# ospi144.net
KiCad netlist of a schematic drawn in EAGLE
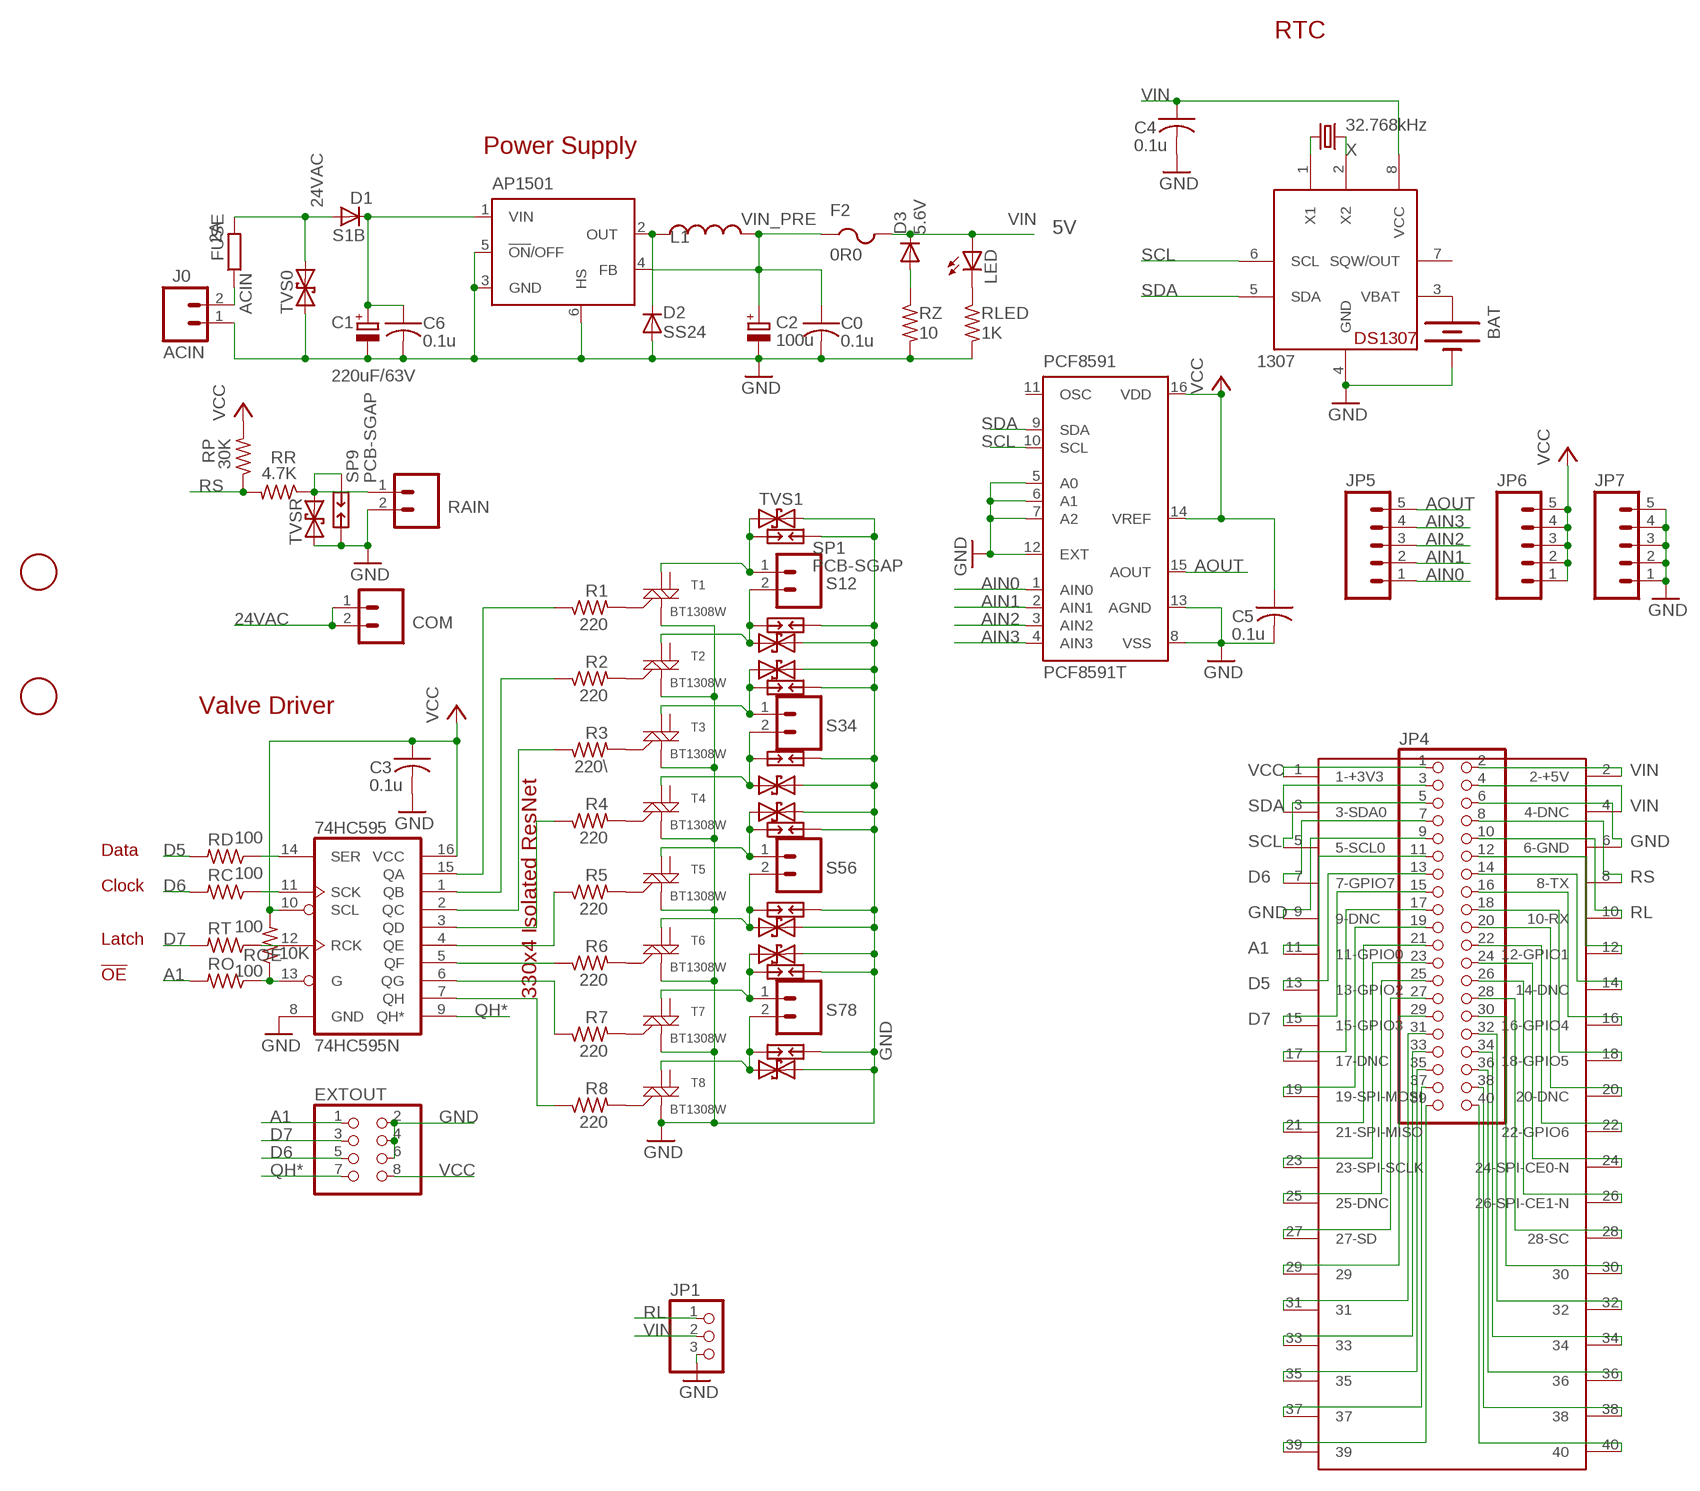
[diagram p0: schematic, sheet 1]

(export (version "E")
  (design (tool "Eeschema 10.0.6"))
  (components
    (comp (ref "74HC595")
      (value "74HC595N")
      (footprint "eagle-import:SO16")
      (libsource (lib "eagle-import") (part "74595DLS"))
    )
    (comp (ref "1307")
      (value "DS1307")
      (footprint "eagle-import:SO08")
      (libsource (lib "eagle-import") (part "DS1307SOIC"))
    )
    (comp (ref "AP1501")
      (value "LM2596S")
      (footprint "eagle-import:TO263-5")
      (fields (field (name "MF") "NATIONAL SEMICONDUCTOR") (field (name "MPN") "LM2596S-ADJ/NOPB"))
      (libsource (lib "eagle-import") (part "LM2596S"))
    )
    (comp (ref "BAT")
      (value "BATTERYBATTERY_12MM_SMT")
      (footprint "eagle-import:BATTCON_12MM_SMT")
      (libsource (lib "eagle-import") (part "BATTERYBATTERY_12MM_SMT"))
    )
    (comp (ref "C0")
      (value "0.1u")
      (footprint "eagle-import:C0603K")
      (libsource (lib "eagle-import") (part "C-USC0603K"))
    )
    (comp (ref "C1")
      (value "220uF/63V")
      (footprint "eagle-import:PANASONIC_E")
      (libsource (lib "eagle-import") (part "CPOL-EUE"))
    )
    (comp (ref "C2")
      (value "100u")
      (footprint "eagle-import:PANASONIC_E")
      (libsource (lib "eagle-import") (part "CPOL-EUE"))
    )
    (comp (ref "C3")
      (value "0.1u")
      (footprint "eagle-import:C0603K")
      (libsource (lib "eagle-import") (part "C-USC0603K"))
    )
    (comp (ref "C4")
      (value "0.1u")
      (footprint "eagle-import:C0603K")
      (libsource (lib "eagle-import") (part "C-USC0603K"))
    )
    (comp (ref "C5")
      (value "0.1u")
      (footprint "eagle-import:C0603K")
      (libsource (lib "eagle-import") (part "C-USC0603K"))
    )
    (comp (ref "C6")
      (value "0.1u")
      (footprint "eagle-import:C0603K")
      (libsource (lib "eagle-import") (part "C-USC0603K"))
    )
    (comp (ref "COM")
      (value "M025MM-X")
      (footprint "eagle-import:SCREWTERMINAL-5MM-2-X")
      (libsource (lib "eagle-import") (part "M025MM-X"))
    )
    (comp (ref "D1")
      (value "S1B")
      (footprint "eagle-import:DO-214AC")
      (libsource (lib "eagle-import") (part "DIODE-DO-214AC"))
    )
    (comp (ref "D2")
      (value "SS24")
      (footprint "eagle-import:SMB")
      (libsource (lib "eagle-import") (part "DIODE-SMB"))
    )
    (comp (ref "D3")
      (value "5.6V")
      (footprint "eagle-import:MINIMELF")
      (libsource (lib "eagle-import") (part "DIODE-MINIMELF"))
    )
    (comp (ref "EXTOUT")
      (value "PINHD-2X4/90")
      (footprint "eagle-import:2X04_90")
      (libsource (lib "eagle-import") (part "PINHD-2X4/90"))
    )
    (comp (ref "F2")
      (value "0R0")
      (footprint "eagle-import:1812")
      (libsource (lib "eagle-import") (part "PTCFUSE-1812"))
    )
    (comp (ref "FUSE")
      (value "2A")
      (footprint "eagle-import:0207_12")
      (libsource (lib "eagle-import") (part "R-EU_0207/12"))
    )
    (comp (ref "J0")
      (value "ACIN")
      (footprint "eagle-import:SCREWTERMINAL-4MM-2-X")
      (libsource (lib "eagle-import") (part "M024MM-X"))
    )
    (comp (ref "JP1")
      (value "PINHD-1X3")
      (footprint "eagle-import:1X03")
      (libsource (lib "eagle-import") (part "PINHD-1X3"))
    )
    (comp (ref "JP4")
      (value "PINHD-2X20")
      (footprint "eagle-import:2X20")
      (libsource (lib "eagle-import") (part "PINHD-2X20"))
    )
    (comp (ref "JP5")
      (value "M05PTH")
      (footprint "eagle-import:1X05")
      (libsource (lib "eagle-import") (part "M05PTH"))
    )
    (comp (ref "JP6")
      (value "M05PTH")
      (footprint "eagle-import:1X05")
      (libsource (lib "eagle-import") (part "M05PTH"))
    )
    (comp (ref "JP7")
      (value "M05PTH")
      (footprint "eagle-import:1X05")
      (libsource (lib "eagle-import") (part "M05PTH"))
    )
    (comp (ref "L1")
      (value "150uH")
      (footprint "eagle-import:CDRH125")
      (libsource (lib "eagle-import") (part "INDUCTORPWR"))
    )
    (comp (ref "LED")
      (value "LEDCHIPLED_0805")
      (footprint "eagle-import:CHIPLED_0805")
      (libsource (lib "eagle-import") (part "LEDCHIPLED_0805"))
    )
    (comp (ref "PCF8591")
      (value "PCF8591T")
      (footprint "eagle-import:SO16W")
      (fields (field (name "MPN") "PCF8591T/2,512"))
      (libsource (lib "eagle-import") (part "PCF8591T"))
    )
    (comp (ref "R1")
      (value "220")
      (footprint "eagle-import:R0603")
      (libsource (lib "eagle-import") (part "R-US_R0603"))
    )
    (comp (ref "R2")
      (value "220")
      (footprint "eagle-import:R0603")
      (libsource (lib "eagle-import") (part "R-US_R0603"))
    )
    (comp (ref "R3")
      (value "220\\")
      (footprint "eagle-import:R0603")
      (libsource (lib "eagle-import") (part "R-US_R0603"))
    )
    (comp (ref "R4")
      (value "220")
      (footprint "eagle-import:R0603")
      (libsource (lib "eagle-import") (part "R-US_R0603"))
    )
    (comp (ref "R5")
      (value "220")
      (footprint "eagle-import:R0603")
      (libsource (lib "eagle-import") (part "R-US_R0603"))
    )
    (comp (ref "R6")
      (value "220")
      (footprint "eagle-import:R0603")
      (libsource (lib "eagle-import") (part "R-US_R0603"))
    )
    (comp (ref "R7")
      (value "220")
      (footprint "eagle-import:R0603")
      (libsource (lib "eagle-import") (part "R-US_R0603"))
    )
    (comp (ref "R8")
      (value "220")
      (footprint "eagle-import:R0603")
      (libsource (lib "eagle-import") (part "R-US_R0603"))
    )
    (comp (ref "RAIN")
      (value "M025MM-X")
      (footprint "eagle-import:SCREWTERMINAL-5MM-2-X")
      (libsource (lib "eagle-import") (part "M025MM-X"))
    )
    (comp (ref "RC")
      (value "100")
      (footprint "eagle-import:R0603")
      (libsource (lib "eagle-import") (part "R-US_R0603"))
    )
    (comp (ref "RD")
      (value "100")
      (footprint "eagle-import:R0603")
      (libsource (lib "eagle-import") (part "R-US_R0603"))
    )
    (comp (ref "RLED")
      (value "1K")
      (footprint "eagle-import:R0805")
      (libsource (lib "eagle-import") (part "R-US_R0805"))
    )
    (comp (ref "RO")
      (value "100")
      (footprint "eagle-import:R0603")
      (libsource (lib "eagle-import") (part "R-US_R0603"))
    )
    (comp (ref "ROE")
      (value "10K")
      (footprint "eagle-import:R0603")
      (libsource (lib "eagle-import") (part "R-US_R0603"))
    )
    (comp (ref "RP")
      (value "30K")
      (footprint "eagle-import:R0805")
      (libsource (lib "eagle-import") (part "R-US_R0805"))
    )
    (comp (ref "RR")
      (value "4.7K")
      (footprint "eagle-import:R0805")
      (libsource (lib "eagle-import") (part "R-US_R0805"))
    )
    (comp (ref "RT")
      (value "100")
      (footprint "eagle-import:R0603")
      (libsource (lib "eagle-import") (part "R-US_R0603"))
    )
    (comp (ref "RZ")
      (value "10")
      (footprint "eagle-import:R2010")
      (libsource (lib "eagle-import") (part "R-US_R2010"))
    )
    (comp (ref "S12")
      (value "M025MM-X")
      (footprint "eagle-import:SCREWTERMINAL-5MM-2-X")
      (libsource (lib "eagle-import") (part "M025MM-X"))
    )
    (comp (ref "S34")
      (value "M025MM-X")
      (footprint "eagle-import:SCREWTERMINAL-5MM-2-X")
      (libsource (lib "eagle-import") (part "M025MM-X"))
    )
    (comp (ref "S56")
      (value "M025MM-X")
      (footprint "eagle-import:SCREWTERMINAL-5MM-2-X")
      (libsource (lib "eagle-import") (part "M025MM-X"))
    )
    (comp (ref "S78")
      (value "M025MM-X")
      (footprint "eagle-import:SCREWTERMINAL-5MM-2-X")
      (libsource (lib "eagle-import") (part "M025MM-X"))
    )
    (comp (ref "SP1")
      (value "PCB-SGAP")
      (footprint "eagle-import:PCB-SGAP")
      (libsource (lib "eagle-import") (part "PCB-SGAP"))
    )
    (comp (ref "SP2")
      (value "PCB-SGAP")
      (footprint "eagle-import:PCB-SGAP")
      (libsource (lib "eagle-import") (part "PCB-SGAP"))
    )
    (comp (ref "SP3")
      (value "PCB-SGAP")
      (footprint "eagle-import:PCB-SGAP")
      (libsource (lib "eagle-import") (part "PCB-SGAP"))
    )
    (comp (ref "SP4")
      (value "PCB-SGAP")
      (footprint "eagle-import:PCB-SGAP")
      (libsource (lib "eagle-import") (part "PCB-SGAP"))
    )
    (comp (ref "SP5")
      (value "PCB-SGAP")
      (footprint "eagle-import:PCB-SGAP")
      (libsource (lib "eagle-import") (part "PCB-SGAP"))
    )
    (comp (ref "SP6")
      (value "PCB-SGAP")
      (footprint "eagle-import:PCB-SGAP")
      (libsource (lib "eagle-import") (part "PCB-SGAP"))
    )
    (comp (ref "SP7")
      (value "PCB-SGAP")
      (footprint "eagle-import:PCB-SGAP")
      (libsource (lib "eagle-import") (part "PCB-SGAP"))
    )
    (comp (ref "SP8")
      (value "PCB-SGAP")
      (footprint "eagle-import:PCB-SGAP")
      (libsource (lib "eagle-import") (part "PCB-SGAP"))
    )
    (comp (ref "SP9")
      (value "PCB-SGAP")
      (footprint "eagle-import:PCB-SGAP")
      (libsource (lib "eagle-import") (part "PCB-SGAP"))
    )
    (comp (ref "T1")
      (value "BT1308W")
      (footprint "eagle-import:SOT223")
      (libsource (lib "eagle-import") (part "MAC97SOT223"))
    )
    (comp (ref "T2")
      (value "BT1308W")
      (footprint "eagle-import:SOT223")
      (libsource (lib "eagle-import") (part "MAC97SOT223"))
    )
    (comp (ref "T3")
      (value "BT1308W")
      (footprint "eagle-import:SOT223")
      (libsource (lib "eagle-import") (part "MAC97SOT223"))
    )
    (comp (ref "T4")
      (value "BT1308W")
      (footprint "eagle-import:SOT223")
      (libsource (lib "eagle-import") (part "MAC97SOT223"))
    )
    (comp (ref "T5")
      (value "BT1308W")
      (footprint "eagle-import:SOT223")
      (libsource (lib "eagle-import") (part "MAC97SOT223"))
    )
    (comp (ref "T6")
      (value "BT1308W")
      (footprint "eagle-import:SOT223")
      (libsource (lib "eagle-import") (part "MAC97SOT223"))
    )
    (comp (ref "T7")
      (value "BT1308W")
      (footprint "eagle-import:SOT223")
      (libsource (lib "eagle-import") (part "MAC97SOT223"))
    )
    (comp (ref "T8")
      (value "BT1308W")
      (footprint "eagle-import:SOT223")
      (libsource (lib "eagle-import") (part "MAC97SOT223"))
    )
    (comp (ref "TVS0")
      (value "TVSSMB")
      (footprint "eagle-import:SMB")
      (libsource (lib "eagle-import") (part "TVSSMB"))
    )
    (comp (ref "TVS1")
      (value "TVSSMB")
      (footprint "eagle-import:SMB")
      (libsource (lib "eagle-import") (part "TVSSMB"))
    )
    (comp (ref "TVS2")
      (value "TVSSMB")
      (footprint "eagle-import:SMB")
      (libsource (lib "eagle-import") (part "TVSSMB"))
    )
    (comp (ref "TVS3")
      (value "TVSSMB")
      (footprint "eagle-import:SMB")
      (libsource (lib "eagle-import") (part "TVSSMB"))
    )
    (comp (ref "TVS4")
      (value "TVSSMB")
      (footprint "eagle-import:SMB")
      (libsource (lib "eagle-import") (part "TVSSMB"))
    )
    (comp (ref "TVS5")
      (value "TVSSMB")
      (footprint "eagle-import:SMB")
      (libsource (lib "eagle-import") (part "TVSSMB"))
    )
    (comp (ref "TVS6")
      (value "TVSSMB")
      (footprint "eagle-import:SMB")
      (libsource (lib "eagle-import") (part "TVSSMB"))
    )
    (comp (ref "TVS7")
      (value "TVSSMB")
      (footprint "eagle-import:SMB")
      (libsource (lib "eagle-import") (part "TVSSMB"))
    )
    (comp (ref "TVS8")
      (value "TVSSMB")
      (footprint "eagle-import:SMB")
      (libsource (lib "eagle-import") (part "TVSSMB"))
    )
    (comp (ref "TVSR")
      (value "TVSSMB")
      (footprint "eagle-import:SMB")
      (libsource (lib "eagle-import") (part "TVSSMB"))
    )
    (comp (ref "U$1")
      (value "FIDUCIAL")
      (footprint "eagle-import:FIDUCIAL_1MM")
      (libsource (lib "eagle-import") (part "FIDUCIAL"))
    )
    (comp (ref "U$2")
      (value "RPIB+")
      (footprint "eagle-import:RPIB+")
      (libsource (lib "eagle-import") (part "RPIB+"))
    )
    (comp (ref "U$3")
      (value "FIDUCIAL")
      (footprint "eagle-import:FIDUCIAL_1MM")
      (libsource (lib "eagle-import") (part "FIDUCIAL"))
    )
    (comp (ref "X")
      (value "32.768kHz")
      (footprint "eagle-import:MM20SS")
      (libsource (lib "eagle-import") (part "CRYSTALMM20SS"))
    )
  )
  (nets
    (net (code "1") (name "/24VAC") (class "Default")
      (node (ref "COM") (pin "1") (pinfunction "1_1") (pintype "passive"))
      (node (ref "COM") (pin "2") (pinfunction "2_2") (pintype "passive"))
      (node (ref "D1") (pin "A") (pinfunction "A_A") (pintype "passive"))
      (node (ref "FUSE") (pin "2") (pinfunction "2_2") (pintype "passive"))
      (node (ref "TVS0") (pin "C") (pinfunction "C_C") (pintype "passive"))
    )
    (net (code "2") (name "/A1") (class "Default")
      (node (ref "EXTOUT") (pin "1") (pinfunction "1_1") (pintype "passive"))
      (node (ref "JP4") (pin "11") (pinfunction "11_11") (pintype "passive"))
      (node (ref "RO") (pin "2") (pinfunction "2_2") (pintype "passive"))
      (node (ref "U$2") (pin "11") (pinfunction "11-GPIO0_11") (pintype "bidirectional"))
    )
    (net (code "3") (name "/ACIN") (class "Default")
      (node (ref "FUSE") (pin "1") (pinfunction "1_1") (pintype "passive"))
      (node (ref "J0") (pin "2") (pinfunction "2_2") (pintype "passive"))
    )
    (net (code "4") (name "/AIN0") (class "Default")
      (node (ref "JP5") (pin "1") (pinfunction "1_1") (pintype "passive"))
      (node (ref "PCF8591") (pin "1") (pinfunction "AIN0_1") (pintype "input"))
    )
    (net (code "5") (name "/AIN1") (class "Default")
      (node (ref "JP5") (pin "2") (pinfunction "2_2") (pintype "passive"))
      (node (ref "PCF8591") (pin "2") (pinfunction "AIN1_2") (pintype "input"))
    )
    (net (code "6") (name "/AIN2") (class "Default")
      (node (ref "JP5") (pin "3") (pinfunction "3_3") (pintype "passive"))
      (node (ref "PCF8591") (pin "3") (pinfunction "AIN2_3") (pintype "input"))
    )
    (net (code "7") (name "/AIN3") (class "Default")
      (node (ref "JP5") (pin "4") (pinfunction "4_4") (pintype "passive"))
      (node (ref "PCF8591") (pin "4") (pinfunction "AIN3_4") (pintype "input"))
    )
    (net (code "8") (name "/AOUT") (class "Default")
      (node (ref "JP5") (pin "5") (pinfunction "5_5") (pintype "passive"))
      (node (ref "PCF8591") (pin "15") (pinfunction "AOUT_15") (pintype "output"))
    )
    (net (code "9") (name "/D5") (class "Default")
      (node (ref "JP4") (pin "13") (pinfunction "13_13") (pintype "passive"))
      (node (ref "RD") (pin "2") (pinfunction "2_2") (pintype "passive"))
      (node (ref "U$2") (pin "13") (pinfunction "13-GPIO2_13") (pintype "bidirectional"))
    )
    (net (code "10") (name "/D6") (class "Default")
      (node (ref "EXTOUT") (pin "5") (pinfunction "5_5") (pintype "passive"))
      (node (ref "JP4") (pin "7") (pinfunction "7_7") (pintype "passive"))
      (node (ref "RC") (pin "2") (pinfunction "2_2") (pintype "passive"))
      (node (ref "U$2") (pin "7") (pinfunction "7-GPIO7_7") (pintype "bidirectional"))
    )
    (net (code "11") (name "/D7") (class "Default")
      (node (ref "EXTOUT") (pin "3") (pinfunction "3_3") (pintype "passive"))
      (node (ref "JP4") (pin "15") (pinfunction "15_15") (pintype "passive"))
      (node (ref "RT") (pin "2") (pinfunction "2_2") (pintype "passive"))
      (node (ref "U$2") (pin "15") (pinfunction "15-GPIO3_15") (pintype "bidirectional"))
    )
    (net (code "12") (name "/QH*") (class "Default")
      (node (ref "74HC595") (pin "9") (pinfunction "QH*_9") (pintype "tri_state"))
      (node (ref "EXTOUT") (pin "7") (pinfunction "7_7") (pintype "passive"))
    )
    (net (code "13") (name "/RL") (class "Default")
      (node (ref "JP1") (pin "1") (pinfunction "1_1") (pintype "passive"))
      (node (ref "JP4") (pin "10") (pinfunction "10_10") (pintype "passive"))
      (node (ref "U$2") (pin "10") (pinfunction "10-RX_10") (pintype "bidirectional"))
    )
    (net (code "14") (name "/RS") (class "Default")
      (node (ref "JP4") (pin "8") (pinfunction "8_8") (pintype "passive"))
      (node (ref "RP") (pin "1") (pinfunction "1_1") (pintype "passive"))
      (node (ref "RR") (pin "2") (pinfunction "2_2") (pintype "passive"))
      (node (ref "U$2") (pin "8") (pinfunction "8-TX_8") (pintype "bidirectional"))
    )
    (net (code "15") (name "/SCL") (class "Default")
      (node (ref "1307") (pin "6") (pinfunction "SCL_6") (pintype "bidirectional"))
      (node (ref "JP4") (pin "5") (pinfunction "5_5") (pintype "passive"))
      (node (ref "PCF8591") (pin "10") (pinfunction "SCL_10") (pintype "input"))
      (node (ref "U$2") (pin "5") (pinfunction "5-SCL0_5") (pintype "bidirectional"))
    )
    (net (code "16") (name "/SDA") (class "Default")
      (node (ref "1307") (pin "5") (pinfunction "SDA_5") (pintype "bidirectional"))
      (node (ref "JP4") (pin "3") (pinfunction "3_3") (pintype "passive"))
      (node (ref "PCF8591") (pin "9") (pinfunction "SDA_9") (pintype "bidirectional"))
      (node (ref "U$2") (pin "3") (pinfunction "3-SDA0_3") (pintype "bidirectional"))
    )
    (net (code "17") (name "/VIN") (class "Default")
      (node (ref "1307") (pin "8") (pinfunction "VCC_8") (pintype "power_in"))
      (node (ref "C4") (pin "1") (pinfunction "1_1") (pintype "passive"))
      (node (ref "D3") (pin "C") (pinfunction "C_C") (pintype "passive"))
      (node (ref "F2") (pin "2") (pinfunction "2_2") (pintype "passive"))
      (node (ref "JP1") (pin "2") (pinfunction "2_2") (pintype "passive"))
      (node (ref "JP4") (pin "2") (pinfunction "2_2") (pintype "passive"))
      (node (ref "JP4") (pin "4") (pinfunction "4_4") (pintype "passive"))
      (node (ref "LED") (pin "A") (pinfunction "A_A") (pintype "passive"))
      (node (ref "U$2") (pin "2") (pinfunction "2-+5V_2") (pintype "bidirectional"))
      (node (ref "U$2") (pin "4") (pinfunction "4-DNC_4") (pintype "bidirectional"))
    )
    (net (code "18") (name "/VIN_PRE") (class "Default")
      (node (ref "AP1501") (pin "4") (pinfunction "FB_4") (pintype "input"))
      (node (ref "C0") (pin "1") (pinfunction "1_1") (pintype "passive"))
      (node (ref "C2") (pin "+") (pinfunction "+_+") (pintype "passive"))
      (node (ref "F2") (pin "1") (pinfunction "1_1") (pintype "passive"))
      (node (ref "L1") (pin "2") (pinfunction "2_2") (pintype "passive"))
    )
    (net (code "19") (name "GND") (class "Default")
      (node (ref "1307") (pin "4") (pinfunction "GND_4") (pintype "power_in"))
      (node (ref "74HC595") (pin "8") (pinfunction "GND_8") (pintype "power_in"))
      (node (ref "AP1501") (pin "3") (pinfunction "GND_3") (pintype "power_in"))
      (node (ref "AP1501") (pin "5") (pinfunction "~{ON}/OFF_5") (pintype "input"))
      (node (ref "AP1501") (pin "6") (pinfunction "HS_6") (pintype "power_in"))
      (node (ref "BAT") (pin "P$1") (pinfunction "-_P$1") (pintype "power_in"))
      (node (ref "C0") (pin "2") (pinfunction "2_2") (pintype "passive"))
      (node (ref "C1") (pin "-") (pinfunction "-_-") (pintype "passive"))
      (node (ref "C2") (pin "-") (pinfunction "-_-") (pintype "passive"))
      (node (ref "C3") (pin "2") (pinfunction "2_2") (pintype "passive"))
      (node (ref "C4") (pin "2") (pinfunction "2_2") (pintype "passive"))
      (node (ref "C5") (pin "2") (pinfunction "2_2") (pintype "passive"))
      (node (ref "C6") (pin "2") (pinfunction "2_2") (pintype "passive"))
      (node (ref "D2") (pin "A") (pinfunction "A_A") (pintype "passive"))
      (node (ref "EXTOUT") (pin "2") (pinfunction "2_2") (pintype "passive"))
      (node (ref "EXTOUT") (pin "4") (pinfunction "4_4") (pintype "passive"))
      (node (ref "EXTOUT") (pin "6") (pinfunction "6_6") (pintype "passive"))
      (node (ref "J0") (pin "1") (pinfunction "1_1") (pintype "passive"))
      (node (ref "JP1") (pin "3") (pinfunction "3_3") (pintype "passive"))
      (node (ref "JP4") (pin "6") (pinfunction "6_6") (pintype "passive"))
      (node (ref "JP4") (pin "9") (pinfunction "9_9") (pintype "passive"))
      (node (ref "JP7") (pin "1") (pinfunction "1_1") (pintype "passive"))
      (node (ref "JP7") (pin "2") (pinfunction "2_2") (pintype "passive"))
      (node (ref "JP7") (pin "3") (pinfunction "3_3") (pintype "passive"))
      (node (ref "JP7") (pin "4") (pinfunction "4_4") (pintype "passive"))
      (node (ref "JP7") (pin "5") (pinfunction "5_5") (pintype "passive"))
      (node (ref "PCF8591") (pin "12") (pinfunction "EXT_12") (pintype "input"))
      (node (ref "PCF8591") (pin "13") (pinfunction "AGND_13") (pintype "power_in"))
      (node (ref "PCF8591") (pin "5") (pinfunction "A0_5") (pintype "input"))
      (node (ref "PCF8591") (pin "6") (pinfunction "A1_6") (pintype "input"))
      (node (ref "PCF8591") (pin "7") (pinfunction "A2_7") (pintype "input"))
      (node (ref "PCF8591") (pin "8") (pinfunction "VSS_8") (pintype "power_in"))
      (node (ref "RAIN") (pin "2") (pinfunction "2_2") (pintype "passive"))
      (node (ref "RLED") (pin "2") (pinfunction "2_2") (pintype "passive"))
      (node (ref "RZ") (pin "2") (pinfunction "2_2") (pintype "passive"))
      (node (ref "SP1") (pin "1") (pinfunction "1_1") (pintype "passive"))
      (node (ref "SP2") (pin "1") (pinfunction "1_1") (pintype "passive"))
      (node (ref "SP3") (pin "1") (pinfunction "1_1") (pintype "passive"))
      (node (ref "SP4") (pin "1") (pinfunction "1_1") (pintype "passive"))
      (node (ref "SP5") (pin "1") (pinfunction "1_1") (pintype "passive"))
      (node (ref "SP6") (pin "1") (pinfunction "1_1") (pintype "passive"))
      (node (ref "SP7") (pin "1") (pinfunction "1_1") (pintype "passive"))
      (node (ref "SP8") (pin "1") (pinfunction "1_1") (pintype "passive"))
      (node (ref "SP9") (pin "2") (pinfunction "2_2") (pintype "passive"))
      (node (ref "T1") (pin "1") (pinfunction "M1_1") (pintype "bidirectional"))
      (node (ref "T2") (pin "1") (pinfunction "M1_1") (pintype "bidirectional"))
      (node (ref "T3") (pin "1") (pinfunction "M1_1") (pintype "bidirectional"))
      (node (ref "T4") (pin "1") (pinfunction "M1_1") (pintype "bidirectional"))
      (node (ref "T5") (pin "1") (pinfunction "M1_1") (pintype "bidirectional"))
      (node (ref "T6") (pin "1") (pinfunction "M1_1") (pintype "bidirectional"))
      (node (ref "T7") (pin "1") (pinfunction "M1_1") (pintype "bidirectional"))
      (node (ref "T8") (pin "1") (pinfunction "M1_1") (pintype "bidirectional"))
      (node (ref "TVS0") (pin "A") (pinfunction "A_A") (pintype "passive"))
      (node (ref "TVS1") (pin "C") (pinfunction "C_C") (pintype "passive"))
      (node (ref "TVS2") (pin "C") (pinfunction "C_C") (pintype "passive"))
      (node (ref "TVS3") (pin "C") (pinfunction "C_C") (pintype "passive"))
      (node (ref "TVS4") (pin "C") (pinfunction "C_C") (pintype "passive"))
      (node (ref "TVS5") (pin "C") (pinfunction "C_C") (pintype "passive"))
      (node (ref "TVS6") (pin "C") (pinfunction "C_C") (pintype "passive"))
      (node (ref "TVS7") (pin "C") (pinfunction "C_C") (pintype "passive"))
      (node (ref "TVS8") (pin "C") (pinfunction "C_C") (pintype "passive"))
      (node (ref "TVSR") (pin "A") (pinfunction "A_A") (pintype "passive"))
      (node (ref "U$2") (pin "6") (pinfunction "6-GND_6") (pintype "bidirectional"))
      (node (ref "U$2") (pin "9") (pinfunction "9-DNC_9") (pintype "bidirectional"))
    )
    (net (code "20") (name "Net-(74HC595-G)") (class "Default")
      (node (ref "74HC595") (pin "13") (pinfunction "G_13") (pintype "input"))
      (node (ref "RO") (pin "1") (pinfunction "1_1") (pintype "passive"))
      (node (ref "ROE") (pin "1") (pinfunction "1_1") (pintype "passive"))
    )
    (net (code "21") (name "Net-(74HC595-QA)") (class "Default")
      (node (ref "74HC595") (pin "15") (pinfunction "QA_15") (pintype "tri_state"))
      (node (ref "R1") (pin "1") (pinfunction "1_1") (pintype "passive"))
    )
    (net (code "22") (name "Net-(74HC595-QB)") (class "Default")
      (node (ref "74HC595") (pin "1") (pinfunction "QB_1") (pintype "tri_state"))
      (node (ref "R2") (pin "1") (pinfunction "1_1") (pintype "passive"))
    )
    (net (code "23") (name "Net-(74HC595-QC)") (class "Default")
      (node (ref "74HC595") (pin "2") (pinfunction "QC_2") (pintype "tri_state"))
      (node (ref "R3") (pin "1") (pinfunction "1_1") (pintype "passive"))
    )
    (net (code "24") (name "Net-(74HC595-QD)") (class "Default")
      (node (ref "74HC595") (pin "3") (pinfunction "QD_3") (pintype "tri_state"))
      (node (ref "R4") (pin "1") (pinfunction "1_1") (pintype "passive"))
    )
    (net (code "25") (name "Net-(74HC595-QE)") (class "Default")
      (node (ref "74HC595") (pin "4") (pinfunction "QE_4") (pintype "tri_state"))
      (node (ref "R5") (pin "1") (pinfunction "1_1") (pintype "passive"))
    )
    (net (code "26") (name "Net-(74HC595-QF)") (class "Default")
      (node (ref "74HC595") (pin "5") (pinfunction "QF_5") (pintype "tri_state"))
      (node (ref "R6") (pin "1") (pinfunction "1_1") (pintype "passive"))
    )
    (net (code "27") (name "Net-(74HC595-QG)") (class "Default")
      (node (ref "74HC595") (pin "6") (pinfunction "QG_6") (pintype "tri_state"))
      (node (ref "R7") (pin "1") (pinfunction "1_1") (pintype "passive"))
    )
    (net (code "28") (name "Net-(74HC595-QH)") (class "Default")
      (node (ref "74HC595") (pin "7") (pinfunction "QH_7") (pintype "tri_state"))
      (node (ref "R8") (pin "1") (pinfunction "1_1") (pintype "passive"))
    )
    (net (code "29") (name "Net-(74HC595-RCK)") (class "Default")
      (node (ref "74HC595") (pin "12") (pinfunction "RCK_12") (pintype "input"))
      (node (ref "RT") (pin "1") (pinfunction "1_1") (pintype "passive"))
    )
    (net (code "30") (name "Net-(74HC595-SCK)") (class "Default")
      (node (ref "74HC595") (pin "11") (pinfunction "SCK_11") (pintype "input"))
      (node (ref "RC") (pin "1") (pinfunction "1_1") (pintype "passive"))
    )
    (net (code "31") (name "Net-(74HC595-SER)") (class "Default")
      (node (ref "74HC595") (pin "14") (pinfunction "SER_14") (pintype "input"))
      (node (ref "RD") (pin "1") (pinfunction "1_1") (pintype "passive"))
    )
    (net (code "32") (name "Net-(1307-VBAT)") (class "Default")
      (node (ref "1307") (pin "3") (pinfunction "VBAT_3") (pintype "power_in"))
      (node (ref "BAT") (pin "P$2") (pinfunction "+_P$2") (pintype "power_in"))
    )
    (net (code "33") (name "Net-(1307-X1)") (class "Default")
      (node (ref "1307") (pin "1") (pinfunction "X1_1") (pintype "passive"))
      (node (ref "X") (pin "1") (pinfunction "1_1") (pintype "passive"))
    )
    (net (code "34") (name "Net-(1307-X2)") (class "Default")
      (node (ref "1307") (pin "2") (pinfunction "X2_2") (pintype "passive"))
      (node (ref "X") (pin "4") (pinfunction "2_4") (pintype "passive"))
    )
    (net (code "35") (name "Net-(AP1501-OUT)") (class "Default")
      (node (ref "AP1501") (pin "2") (pinfunction "OUT_2") (pintype "output"))
      (node (ref "D2") (pin "C") (pinfunction "C_C") (pintype "passive"))
      (node (ref "L1") (pin "1") (pinfunction "1_1") (pintype "passive"))
    )
    (net (code "36") (name "Net-(AP1501-VIN)") (class "Default")
      (node (ref "AP1501") (pin "1") (pinfunction "VIN_1") (pintype "input"))
      (node (ref "C1") (pin "+") (pinfunction "+_+") (pintype "passive"))
      (node (ref "C6") (pin "1") (pinfunction "1_1") (pintype "passive"))
      (node (ref "D1") (pin "C") (pinfunction "C_C") (pintype "passive"))
    )
    (net (code "37") (name "Net-(D3-PadA)") (class "Default")
      (node (ref "D3") (pin "A") (pinfunction "A_A") (pintype "passive"))
      (node (ref "RZ") (pin "1") (pinfunction "1_1") (pintype "passive"))
    )
    (net (code "38") (name "Net-(JP4-Pad29)") (class "Default")
      (node (ref "JP4") (pin "29") (pinfunction "29_29") (pintype "passive"))
      (node (ref "U$2") (pin "29") (pinfunction "29_29") (pintype "bidirectional"))
    )
    (net (code "39") (name "Net-(JP4-Pad30)") (class "Default")
      (node (ref "JP4") (pin "30") (pinfunction "30_30") (pintype "passive"))
      (node (ref "U$2") (pin "30") (pinfunction "30_30") (pintype "bidirectional"))
    )
    (net (code "40") (name "Net-(JP4-Pad31)") (class "Default")
      (node (ref "JP4") (pin "31") (pinfunction "31_31") (pintype "passive"))
      (node (ref "U$2") (pin "31") (pinfunction "31_31") (pintype "bidirectional"))
    )
    (net (code "41") (name "Net-(JP4-Pad32)") (class "Default")
      (node (ref "JP4") (pin "32") (pinfunction "32_32") (pintype "passive"))
      (node (ref "U$2") (pin "32") (pinfunction "32_32") (pintype "bidirectional"))
    )
    (net (code "42") (name "Net-(JP4-Pad33)") (class "Default")
      (node (ref "JP4") (pin "33") (pinfunction "33_33") (pintype "passive"))
      (node (ref "U$2") (pin "33") (pinfunction "33_33") (pintype "bidirectional"))
    )
    (net (code "43") (name "Net-(JP4-Pad34)") (class "Default")
      (node (ref "JP4") (pin "34") (pinfunction "34_34") (pintype "passive"))
      (node (ref "U$2") (pin "34") (pinfunction "34_34") (pintype "bidirectional"))
    )
    (net (code "44") (name "Net-(JP4-Pad35)") (class "Default")
      (node (ref "JP4") (pin "35") (pinfunction "35_35") (pintype "passive"))
      (node (ref "U$2") (pin "35") (pinfunction "35_35") (pintype "bidirectional"))
    )
    (net (code "45") (name "Net-(JP4-Pad36)") (class "Default")
      (node (ref "JP4") (pin "36") (pinfunction "36_36") (pintype "passive"))
      (node (ref "U$2") (pin "36") (pinfunction "36_36") (pintype "bidirectional"))
    )
    (net (code "46") (name "Net-(JP4-Pad37)") (class "Default")
      (node (ref "JP4") (pin "37") (pinfunction "37_37") (pintype "passive"))
      (node (ref "U$2") (pin "37") (pinfunction "37_37") (pintype "bidirectional"))
    )
    (net (code "47") (name "Net-(JP4-Pad38)") (class "Default")
      (node (ref "JP4") (pin "38") (pinfunction "38_38") (pintype "passive"))
      (node (ref "U$2") (pin "38") (pinfunction "38_38") (pintype "bidirectional"))
    )
    (net (code "48") (name "Net-(JP4-Pad39)") (class "Default")
      (node (ref "JP4") (pin "39") (pinfunction "39_39") (pintype "passive"))
      (node (ref "U$2") (pin "39") (pinfunction "39_39") (pintype "bidirectional"))
    )
    (net (code "49") (name "Net-(JP4-Pad40)") (class "Default")
      (node (ref "JP4") (pin "40") (pinfunction "40_40") (pintype "passive"))
      (node (ref "U$2") (pin "40") (pinfunction "40_40") (pintype "bidirectional"))
    )
    (net (code "50") (name "Net-(LED-PadC)") (class "Default")
      (node (ref "LED") (pin "C") (pinfunction "C_C") (pintype "passive"))
      (node (ref "RLED") (pin "1") (pinfunction "1_1") (pintype "passive"))
    )
    (net (code "51") (name "Net-(RAIN-Pad1)") (class "Default")
      (node (ref "RAIN") (pin "1") (pinfunction "1_1") (pintype "passive"))
      (node (ref "RR") (pin "1") (pinfunction "1_1") (pintype "passive"))
      (node (ref "SP9") (pin "1") (pinfunction "1_1") (pintype "passive"))
      (node (ref "TVSR") (pin "C") (pinfunction "C_C") (pintype "passive"))
    )
    (net (code "52") (name "Net-(T1-G)") (class "Default")
      (node (ref "R1") (pin "2") (pinfunction "2_2") (pintype "passive"))
      (node (ref "T1") (pin "3") (pinfunction "G_3") (pintype "bidirectional"))
    )
    (net (code "53") (name "Net-(T1-M2)") (class "Default")
      (node (ref "S12") (pin "1") (pinfunction "1_1") (pintype "passive"))
      (node (ref "SP1") (pin "2") (pinfunction "2_2") (pintype "passive"))
      (node (ref "T1") (pin "2") (pinfunction "M2_2") (pintype "bidirectional"))
      (node (ref "TVS1") (pin "A") (pinfunction "A_A") (pintype "passive"))
    )
    (net (code "54") (name "Net-(T2-G)") (class "Default")
      (node (ref "R2") (pin "2") (pinfunction "2_2") (pintype "passive"))
      (node (ref "T2") (pin "3") (pinfunction "G_3") (pintype "bidirectional"))
    )
    (net (code "55") (name "Net-(T2-M2)") (class "Default")
      (node (ref "S12") (pin "2") (pinfunction "2_2") (pintype "passive"))
      (node (ref "SP2") (pin "2") (pinfunction "2_2") (pintype "passive"))
      (node (ref "T2") (pin "2") (pinfunction "M2_2") (pintype "bidirectional"))
      (node (ref "TVS2") (pin "A") (pinfunction "A_A") (pintype "passive"))
    )
    (net (code "56") (name "Net-(T3-G)") (class "Default")
      (node (ref "R3") (pin "2") (pinfunction "2_2") (pintype "passive"))
      (node (ref "T3") (pin "3") (pinfunction "G_3") (pintype "bidirectional"))
    )
    (net (code "57") (name "Net-(T3-M2)") (class "Default")
      (node (ref "S34") (pin "1") (pinfunction "1_1") (pintype "passive"))
      (node (ref "SP3") (pin "2") (pinfunction "2_2") (pintype "passive"))
      (node (ref "T3") (pin "2") (pinfunction "M2_2") (pintype "bidirectional"))
      (node (ref "TVS3") (pin "A") (pinfunction "A_A") (pintype "passive"))
    )
    (net (code "58") (name "Net-(T4-G)") (class "Default")
      (node (ref "R4") (pin "2") (pinfunction "2_2") (pintype "passive"))
      (node (ref "T4") (pin "3") (pinfunction "G_3") (pintype "bidirectional"))
    )
    (net (code "59") (name "Net-(T4-M2)") (class "Default")
      (node (ref "S34") (pin "2") (pinfunction "2_2") (pintype "passive"))
      (node (ref "SP4") (pin "2") (pinfunction "2_2") (pintype "passive"))
      (node (ref "T4") (pin "2") (pinfunction "M2_2") (pintype "bidirectional"))
      (node (ref "TVS4") (pin "A") (pinfunction "A_A") (pintype "passive"))
    )
    (net (code "60") (name "Net-(T5-G)") (class "Default")
      (node (ref "R5") (pin "2") (pinfunction "2_2") (pintype "passive"))
      (node (ref "T5") (pin "3") (pinfunction "G_3") (pintype "bidirectional"))
    )
    (net (code "61") (name "Net-(T5-M2)") (class "Default")
      (node (ref "S56") (pin "1") (pinfunction "1_1") (pintype "passive"))
      (node (ref "SP5") (pin "2") (pinfunction "2_2") (pintype "passive"))
      (node (ref "T5") (pin "2") (pinfunction "M2_2") (pintype "bidirectional"))
      (node (ref "TVS5") (pin "A") (pinfunction "A_A") (pintype "passive"))
    )
    (net (code "62") (name "Net-(T6-G)") (class "Default")
      (node (ref "R6") (pin "2") (pinfunction "2_2") (pintype "passive"))
      (node (ref "T6") (pin "3") (pinfunction "G_3") (pintype "bidirectional"))
    )
    (net (code "63") (name "Net-(T6-M2)") (class "Default")
      (node (ref "S56") (pin "2") (pinfunction "2_2") (pintype "passive"))
      (node (ref "SP6") (pin "2") (pinfunction "2_2") (pintype "passive"))
      (node (ref "T6") (pin "2") (pinfunction "M2_2") (pintype "bidirectional"))
      (node (ref "TVS6") (pin "A") (pinfunction "A_A") (pintype "passive"))
    )
    (net (code "64") (name "Net-(T7-G)") (class "Default")
      (node (ref "R7") (pin "2") (pinfunction "2_2") (pintype "passive"))
      (node (ref "T7") (pin "3") (pinfunction "G_3") (pintype "bidirectional"))
    )
    (net (code "65") (name "Net-(T7-M2)") (class "Default")
      (node (ref "S78") (pin "1") (pinfunction "1_1") (pintype "passive"))
      (node (ref "SP7") (pin "2") (pinfunction "2_2") (pintype "passive"))
      (node (ref "T7") (pin "2") (pinfunction "M2_2") (pintype "bidirectional"))
      (node (ref "TVS7") (pin "A") (pinfunction "A_A") (pintype "passive"))
    )
    (net (code "66") (name "Net-(T8-G)") (class "Default")
      (node (ref "R8") (pin "2") (pinfunction "2_2") (pintype "passive"))
      (node (ref "T8") (pin "3") (pinfunction "G_3") (pintype "bidirectional"))
    )
    (net (code "67") (name "Net-(T8-M2)") (class "Default")
      (node (ref "S78") (pin "2") (pinfunction "2_2") (pintype "passive"))
      (node (ref "SP8") (pin "2") (pinfunction "2_2") (pintype "passive"))
      (node (ref "T8") (pin "2") (pinfunction "M2_2") (pintype "bidirectional"))
      (node (ref "TVS8") (pin "A") (pinfunction "A_A") (pintype "passive"))
    )
    (net (code "68") (name "Net-(U$2-12-GPIO1)") (class "Default")
      (node (ref "JP4") (pin "12") (pinfunction "12_12") (pintype "passive"))
      (node (ref "U$2") (pin "12") (pinfunction "12-GPIO1_12") (pintype "bidirectional"))
    )
    (net (code "69") (name "Net-(U$2-14-DNC)") (class "Default")
      (node (ref "JP4") (pin "14") (pinfunction "14_14") (pintype "passive"))
      (node (ref "U$2") (pin "14") (pinfunction "14-DNC_14") (pintype "bidirectional"))
    )
    (net (code "70") (name "Net-(U$2-16-GPIO4)") (class "Default")
      (node (ref "JP4") (pin "16") (pinfunction "16_16") (pintype "passive"))
      (node (ref "U$2") (pin "16") (pinfunction "16-GPIO4_16") (pintype "bidirectional"))
    )
    (net (code "71") (name "Net-(U$2-17-DNC)") (class "Default")
      (node (ref "JP4") (pin "17") (pinfunction "17_17") (pintype "passive"))
      (node (ref "U$2") (pin "17") (pinfunction "17-DNC_17") (pintype "bidirectional"))
    )
    (net (code "72") (name "Net-(U$2-18-GPIO5)") (class "Default")
      (node (ref "JP4") (pin "18") (pinfunction "18_18") (pintype "passive"))
      (node (ref "U$2") (pin "18") (pinfunction "18-GPIO5_18") (pintype "bidirectional"))
    )
    (net (code "73") (name "Net-(U$2-19-SPI-MOSI)") (class "Default")
      (node (ref "JP4") (pin "19") (pinfunction "19_19") (pintype "passive"))
      (node (ref "U$2") (pin "19") (pinfunction "19-SPI-MOSI_19") (pintype "bidirectional"))
    )
    (net (code "74") (name "Net-(U$2-20-DNC)") (class "Default")
      (node (ref "JP4") (pin "20") (pinfunction "20_20") (pintype "passive"))
      (node (ref "U$2") (pin "20") (pinfunction "20-DNC_20") (pintype "bidirectional"))
    )
    (net (code "75") (name "Net-(U$2-21-SPI-MISO)") (class "Default")
      (node (ref "JP4") (pin "21") (pinfunction "21_21") (pintype "passive"))
      (node (ref "U$2") (pin "21") (pinfunction "21-SPI-MISO_21") (pintype "bidirectional"))
    )
    (net (code "76") (name "Net-(U$2-22-GPIO6)") (class "Default")
      (node (ref "JP4") (pin "22") (pinfunction "22_22") (pintype "passive"))
      (node (ref "U$2") (pin "22") (pinfunction "22-GPIO6_22") (pintype "bidirectional"))
    )
    (net (code "77") (name "Net-(U$2-23-SPI-SCLK)") (class "Default")
      (node (ref "JP4") (pin "23") (pinfunction "23_23") (pintype "passive"))
      (node (ref "U$2") (pin "23") (pinfunction "23-SPI-SCLK_23") (pintype "bidirectional"))
    )
    (net (code "78") (name "Net-(U$2-24-SPI-CE0-N)") (class "Default")
      (node (ref "JP4") (pin "24") (pinfunction "24_24") (pintype "passive"))
      (node (ref "U$2") (pin "24") (pinfunction "24-SPI-CE0-N_24") (pintype "bidirectional"))
    )
    (net (code "79") (name "Net-(U$2-25-DNC)") (class "Default")
      (node (ref "JP4") (pin "25") (pinfunction "25_25") (pintype "passive"))
      (node (ref "U$2") (pin "25") (pinfunction "25-DNC_25") (pintype "bidirectional"))
    )
    (net (code "80") (name "Net-(U$2-26-SPI-CE1-N)") (class "Default")
      (node (ref "JP4") (pin "26") (pinfunction "26_26") (pintype "passive"))
      (node (ref "U$2") (pin "26") (pinfunction "26-SPI-CE1-N_26") (pintype "bidirectional"))
    )
    (net (code "81") (name "Net-(U$2-27-SD)") (class "Default")
      (node (ref "JP4") (pin "27") (pinfunction "27_27") (pintype "passive"))
      (node (ref "U$2") (pin "27") (pinfunction "27-SD_27") (pintype "bidirectional"))
    )
    (net (code "82") (name "Net-(U$2-28-SC)") (class "Default")
      (node (ref "JP4") (pin "28") (pinfunction "28_28") (pintype "passive"))
      (node (ref "U$2") (pin "28") (pinfunction "28-SC_28") (pintype "bidirectional"))
    )
    (net (code "83") (name "VCC") (class "Default")
      (node (ref "74HC595") (pin "10") (pinfunction "SCL_10") (pintype "input"))
      (node (ref "74HC595") (pin "16") (pinfunction "VCC_16") (pintype "power_in"))
      (node (ref "C3") (pin "1") (pinfunction "1_1") (pintype "passive"))
      (node (ref "C5") (pin "1") (pinfunction "1_1") (pintype "passive"))
      (node (ref "EXTOUT") (pin "8") (pinfunction "8_8") (pintype "passive"))
      (node (ref "JP4") (pin "1") (pinfunction "1_1") (pintype "passive"))
      (node (ref "JP6") (pin "1") (pinfunction "1_1") (pintype "passive"))
      (node (ref "JP6") (pin "2") (pinfunction "2_2") (pintype "passive"))
      (node (ref "JP6") (pin "3") (pinfunction "3_3") (pintype "passive"))
      (node (ref "JP6") (pin "4") (pinfunction "4_4") (pintype "passive"))
      (node (ref "JP6") (pin "5") (pinfunction "5_5") (pintype "passive"))
      (node (ref "PCF8591") (pin "14") (pinfunction "VREF_14") (pintype "input"))
      (node (ref "PCF8591") (pin "16") (pinfunction "VDD_16") (pintype "power_in"))
      (node (ref "ROE") (pin "2") (pinfunction "2_2") (pintype "passive"))
      (node (ref "RP") (pin "2") (pinfunction "2_2") (pintype "passive"))
      (node (ref "U$2") (pin "1") (pinfunction "1-+3V3_1") (pintype "bidirectional"))
    )
    (net (code "84") (name "unconnected-(1307-SQW{slash}OUT-Pad7)") (class "Default")
      (node (ref "1307") (pin "7") (pinfunction "SQW/OUT_7") (pintype "bidirectional"))
    )
    (net (code "85") (name "unconnected-(PCF8591-OSC-Pad11)") (class "Default")
      (node (ref "PCF8591") (pin "11") (pinfunction "OSC_11") (pintype "input"))
    )
    (net (code "86") (name "unconnected-(T1-M2-4-Pad4)") (class "Default")
      (node (ref "T1") (pin "4") (pinfunction "M2-4_4") (pintype "bidirectional"))
    )
    (net (code "87") (name "unconnected-(T2-M2-4-Pad4)") (class "Default")
      (node (ref "T2") (pin "4") (pinfunction "M2-4_4") (pintype "bidirectional"))
    )
    (net (code "88") (name "unconnected-(T3-M2-4-Pad4)") (class "Default")
      (node (ref "T3") (pin "4") (pinfunction "M2-4_4") (pintype "bidirectional"))
    )
    (net (code "89") (name "unconnected-(T4-M2-4-Pad4)") (class "Default")
      (node (ref "T4") (pin "4") (pinfunction "M2-4_4") (pintype "bidirectional"))
    )
    (net (code "90") (name "unconnected-(T5-M2-4-Pad4)") (class "Default")
      (node (ref "T5") (pin "4") (pinfunction "M2-4_4") (pintype "bidirectional"))
    )
    (net (code "91") (name "unconnected-(T6-M2-4-Pad4)") (class "Default")
      (node (ref "T6") (pin "4") (pinfunction "M2-4_4") (pintype "bidirectional"))
    )
    (net (code "92") (name "unconnected-(T7-M2-4-Pad4)") (class "Default")
      (node (ref "T7") (pin "4") (pinfunction "M2-4_4") (pintype "bidirectional"))
    )
    (net (code "93") (name "unconnected-(T8-M2-4-Pad4)") (class "Default")
      (node (ref "T8") (pin "4") (pinfunction "M2-4_4") (pintype "bidirectional"))
    )
  )
)
